# Adafruit_MLX90393_QT.net
KiCad netlist of a schematic drawn in EAGLE
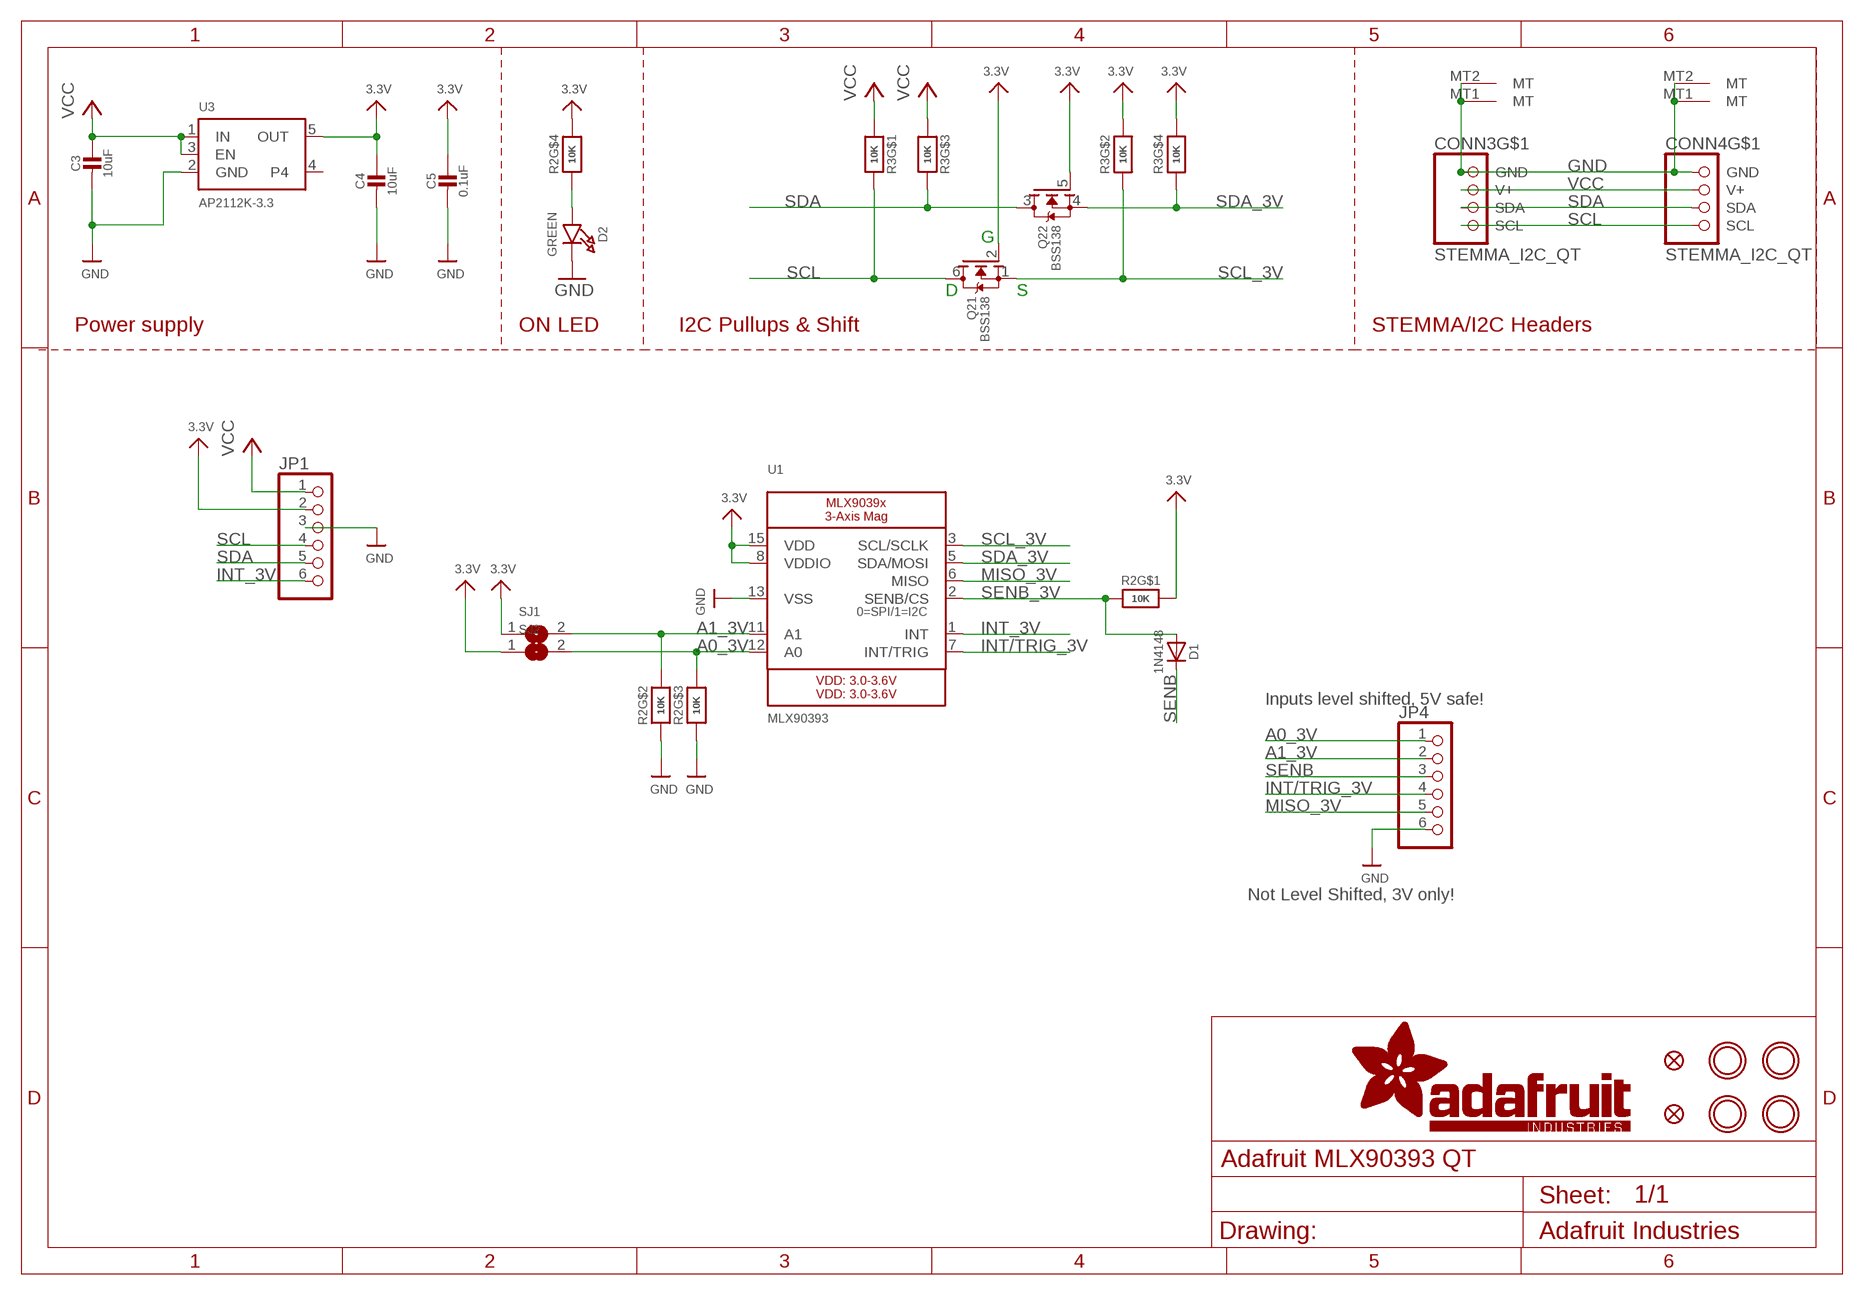
[diagram p0: schematic, sheet 1]

(export (version "E")
  (design (tool "Eeschema 10.0.6"))
  (components
    (comp (ref "C3")
      (value "10uF")
      (footprint "eagle-import:0805-NO")
      (libsource (lib "eagle-import") (part "CAP_CERAMIC0805-NOOUTLINE"))
    )
    (comp (ref "C4")
      (value "10uF")
      (footprint "eagle-import:0805-NO")
      (libsource (lib "eagle-import") (part "CAP_CERAMIC0805-NOOUTLINE"))
    )
    (comp (ref "C5")
      (value "0.1uF")
      (footprint "eagle-import:0603-NO")
      (libsource (lib "eagle-import") (part "CAP_CERAMIC0603_NO"))
    )
    (comp (ref "CONN3")
      (value "STEMMA_I2C_QT")
      (footprint "eagle-import:JST_SH4")
      (libsource (lib "eagle-import") (part "STEMMA_I2C_QT"))
    )
    (comp (ref "CONN4")
      (value "STEMMA_I2C_QT")
      (footprint "eagle-import:JST_SH4")
      (libsource (lib "eagle-import") (part "STEMMA_I2C_QT"))
    )
    (comp (ref "D1")
      (value "1N4148")
      (footprint "eagle-import:SOD-323_MINI")
      (libsource (lib "eagle-import") (part "DIODE_SOD323MINI"))
    )
    (comp (ref "D2")
      (value "GREEN")
      (footprint "eagle-import:CHIPLED_0603_NOOUTLINE")
      (libsource (lib "eagle-import") (part "LED0603_NOOUTLINE"))
    )
    (comp (ref "FID2")
      (value "FIDUCIAL_1MM")
      (footprint "eagle-import:FIDUCIAL_1MM")
      (libsource (lib "eagle-import") (part "FIDUCIAL_1MM"))
    )
    (comp (ref "FID4")
      (value "FIDUCIAL_1MM")
      (footprint "eagle-import:FIDUCIAL_1MM")
      (libsource (lib "eagle-import") (part "FIDUCIAL_1MM"))
    )
    (comp (ref "JP1")
      (value "HEADER-1X670MIL")
      (footprint "eagle-import:1X06_ROUND_70")
      (libsource (lib "eagle-import") (part "HEADER-1X670MIL"))
    )
    (comp (ref "JP4")
      (value "HEADER-1X670MIL")
      (footprint "eagle-import:1X06_ROUND_70")
      (libsource (lib "eagle-import") (part "HEADER-1X670MIL"))
    )
    (comp (ref "Q2")
      (value "BSS138")
      (footprint "eagle-import:SOT363")
      (libsource (lib "eagle-import") (part "MOSFET-N_DUAL"))
    )
    (comp (ref "R2")
      (value "10K")
      (footprint "eagle-import:RESPACK_4X0603_NO")
      (libsource (lib "eagle-import") (part "RESISTOR_4PACK_NO"))
    )
    (comp (ref "R3")
      (value "10K")
      (footprint "eagle-import:RESPACK_4X0603")
      (libsource (lib "eagle-import") (part "RESISTOR_4PACK"))
    )
    (comp (ref "SJ1")
      (value "SOLDERJUMPER")
      (footprint "eagle-import:SOLDERJUMPER_ARROW_NOPASTE")
      (libsource (lib "eagle-import") (part "SOLDERJUMPER"))
    )
    (comp (ref "SJ2")
      (value "SOLDERJUMPER")
      (footprint "eagle-import:SOLDERJUMPER_ARROW_NOPASTE")
      (libsource (lib "eagle-import") (part "SOLDERJUMPER"))
    )
    (comp (ref "U$33")
      (value "MOUNTINGHOLE2.5")
      (footprint "eagle-import:MOUNTINGHOLE_2.5_PLATED")
      (libsource (lib "eagle-import") (part "MOUNTINGHOLE2.5"))
    )
    (comp (ref "U$34")
      (value "MOUNTINGHOLE2.5")
      (footprint "eagle-import:MOUNTINGHOLE_2.5_PLATED")
      (libsource (lib "eagle-import") (part "MOUNTINGHOLE2.5"))
    )
    (comp (ref "U$36")
      (value "MOUNTINGHOLE2.5")
      (footprint "eagle-import:MOUNTINGHOLE_2.5_PLATED")
      (libsource (lib "eagle-import") (part "MOUNTINGHOLE2.5"))
    )
    (comp (ref "U$37")
      (value "MOUNTINGHOLE2.5")
      (footprint "eagle-import:MOUNTINGHOLE_2.5_PLATED")
      (libsource (lib "eagle-import") (part "MOUNTINGHOLE2.5"))
    )
    (comp (ref "U1")
      (value "MLX90393")
      (footprint "eagle-import:QFN16_3MM")
      (libsource (lib "eagle-import") (part "MLX90393"))
    )
    (comp (ref "U3")
      (value "AP2112K-3.3")
      (footprint "eagle-import:SOT23-5")
      (libsource (lib "eagle-import") (part "VREG_SOT23-5"))
    )
  )
  (nets
    (net (code "1") (name "/A0_3V") (class "Default")
      (node (ref "JP4") (pin "1") (pinfunction "1_1") (pintype "passive"))
      (node (ref "R2") (pin "6") (pinfunction "2_6") (pintype "passive"))
      (node (ref "SJ2") (pin "2") (pinfunction "2_2") (pintype "passive"))
      (node (ref "U1") (pin "12") (pinfunction "A0_12") (pintype "input"))
    )
    (net (code "2") (name "/A1_3V") (class "Default")
      (node (ref "JP4") (pin "2") (pinfunction "2_2") (pintype "passive"))
      (node (ref "R2") (pin "7") (pinfunction "2_7") (pintype "passive"))
      (node (ref "SJ1") (pin "2") (pinfunction "2_2") (pintype "passive"))
      (node (ref "U1") (pin "11") (pinfunction "A1_11") (pintype "input"))
    )
    (net (code "3") (name "/INT_3V") (class "Default")
      (node (ref "JP1") (pin "6") (pinfunction "6_6") (pintype "passive"))
      (node (ref "U1") (pin "1") (pinfunction "INT_1") (pintype "output"))
    )
    (net (code "4") (name "/INT{slash}TRIG_3V") (class "Default")
      (node (ref "JP4") (pin "4") (pinfunction "4_4") (pintype "passive"))
      (node (ref "U1") (pin "7") (pinfunction "INT/TRIG_7") (pintype "bidirectional"))
    )
    (net (code "5") (name "/MISO_3V") (class "Default")
      (node (ref "JP4") (pin "5") (pinfunction "5_5") (pintype "passive"))
      (node (ref "U1") (pin "6") (pinfunction "MISO_6") (pintype "output"))
    )
    (net (code "6") (name "/SCL") (class "Default")
      (node (ref "CONN3") (pin "4") (pinfunction "SCL_4") (pintype "passive"))
      (node (ref "CONN4") (pin "4") (pinfunction "SCL_4") (pintype "passive"))
      (node (ref "JP1") (pin "4") (pinfunction "4_4") (pintype "passive"))
      (node (ref "Q2") (pin "6") (pinfunction "D_6") (pintype "bidirectional"))
      (node (ref "R3") (pin "8") (pinfunction "2_8") (pintype "passive"))
    )
    (net (code "7") (name "/SCL_3V") (class "Default")
      (node (ref "Q2") (pin "1") (pinfunction "S_1") (pintype "bidirectional"))
      (node (ref "R3") (pin "7") (pinfunction "2_7") (pintype "passive"))
      (node (ref "U1") (pin "3") (pinfunction "SCL/SCLK_3") (pintype "input"))
    )
    (net (code "8") (name "/SDA") (class "Default")
      (node (ref "CONN3") (pin "3") (pinfunction "SDA_3") (pintype "passive"))
      (node (ref "CONN4") (pin "3") (pinfunction "SDA_3") (pintype "passive"))
      (node (ref "JP1") (pin "5") (pinfunction "5_5") (pintype "passive"))
      (node (ref "Q2") (pin "3") (pinfunction "D_3") (pintype "bidirectional"))
      (node (ref "R3") (pin "6") (pinfunction "2_6") (pintype "passive"))
    )
    (net (code "9") (name "/SDA_3V") (class "Default")
      (node (ref "Q2") (pin "4") (pinfunction "S_4") (pintype "bidirectional"))
      (node (ref "R3") (pin "5") (pinfunction "2_5") (pintype "passive"))
      (node (ref "U1") (pin "5") (pinfunction "SDA/MOSI_5") (pintype "bidirectional"))
    )
    (net (code "10") (name "/SENB") (class "Default")
      (node (ref "D1") (pin "C") (pinfunction "C_C") (pintype "passive"))
      (node (ref "JP4") (pin "3") (pinfunction "3_3") (pintype "passive"))
    )
    (net (code "11") (name "/SENB_3V") (class "Default")
      (node (ref "D1") (pin "A") (pinfunction "A_A") (pintype "passive"))
      (node (ref "R2") (pin "1") (pinfunction "1_1") (pintype "passive"))
      (node (ref "U1") (pin "2") (pinfunction "SENB/CS_2") (pintype "input"))
    )
    (net (code "12") (name "3.3V") (class "Default")
      (node (ref "C4") (pin "1") (pinfunction "1_1") (pintype "passive"))
      (node (ref "C5") (pin "1") (pinfunction "1_1") (pintype "passive"))
      (node (ref "JP1") (pin "2") (pinfunction "2_2") (pintype "passive"))
      (node (ref "Q2") (pin "2") (pinfunction "G_2") (pintype "bidirectional"))
      (node (ref "Q2") (pin "5") (pinfunction "G_5") (pintype "bidirectional"))
      (node (ref "R2") (pin "5") (pinfunction "2_5") (pintype "passive"))
      (node (ref "R2") (pin "8") (pinfunction "2_8") (pintype "passive"))
      (node (ref "R3") (pin "2") (pinfunction "1_2") (pintype "passive"))
      (node (ref "R3") (pin "4") (pinfunction "1_4") (pintype "passive"))
      (node (ref "SJ1") (pin "1") (pinfunction "1_1") (pintype "passive"))
      (node (ref "SJ2") (pin "1") (pinfunction "1_1") (pintype "passive"))
      (node (ref "U1") (pin "15") (pinfunction "VDD_15") (pintype "power_in"))
      (node (ref "U1") (pin "8") (pinfunction "VDDIO_8") (pintype "power_in"))
      (node (ref "U3") (pin "5") (pinfunction "OUT_5") (pintype "power_in"))
    )
    (net (code "13") (name "GND") (class "Default")
      (node (ref "C3") (pin "2") (pinfunction "2_2") (pintype "passive"))
      (node (ref "C4") (pin "2") (pinfunction "2_2") (pintype "passive"))
      (node (ref "C5") (pin "2") (pinfunction "2_2") (pintype "passive"))
      (node (ref "CONN3") (pin "1") (pinfunction "GND_1") (pintype "passive"))
      (node (ref "CONN3") (pin "MT1") (pinfunction "MT_MT1") (pintype "bidirectional"))
      (node (ref "CONN3") (pin "MT2") (pinfunction "MT_MT2") (pintype "bidirectional"))
      (node (ref "CONN4") (pin "1") (pinfunction "GND_1") (pintype "passive"))
      (node (ref "CONN4") (pin "MT1") (pinfunction "MT_MT1") (pintype "bidirectional"))
      (node (ref "CONN4") (pin "MT2") (pinfunction "MT_MT2") (pintype "bidirectional"))
      (node (ref "D2") (pin "C") (pinfunction "C_C") (pintype "passive"))
      (node (ref "JP1") (pin "3") (pinfunction "3_3") (pintype "passive"))
      (node (ref "JP4") (pin "6") (pinfunction "6_6") (pintype "passive"))
      (node (ref "R2") (pin "2") (pinfunction "1_2") (pintype "passive"))
      (node (ref "R2") (pin "3") (pinfunction "1_3") (pintype "passive"))
      (node (ref "U1") (pin "13") (pinfunction "VSS_13") (pintype "power_in"))
      (node (ref "U3") (pin "2") (pinfunction "GND_2") (pintype "power_in"))
    )
    (net (code "14") (name "Net-(R2D-1)") (class "Default")
      (node (ref "D2") (pin "A") (pinfunction "A_A") (pintype "passive"))
      (node (ref "R2") (pin "4") (pinfunction "1_4") (pintype "passive"))
    )
    (net (code "15") (name "VCC") (class "Default")
      (node (ref "C3") (pin "1") (pinfunction "1_1") (pintype "passive"))
      (node (ref "CONN3") (pin "2") (pinfunction "V+_2") (pintype "passive"))
      (node (ref "CONN4") (pin "2") (pinfunction "V+_2") (pintype "passive"))
      (node (ref "JP1") (pin "1") (pinfunction "1_1") (pintype "passive"))
      (node (ref "R3") (pin "1") (pinfunction "1_1") (pintype "passive"))
      (node (ref "R3") (pin "3") (pinfunction "1_3") (pintype "passive"))
      (node (ref "U3") (pin "1") (pinfunction "IN_1") (pintype "power_in"))
      (node (ref "U3") (pin "3") (pinfunction "EN_3") (pintype "input"))
    )
    (net (code "16") (name "unconnected-(U3-P4-Pad4)") (class "Default")
      (node (ref "U3") (pin "4") (pinfunction "P4_4") (pintype "bidirectional"))
    )
  )
)
